# STM32F103RCT6.net
KiCad netlist of a schematic drawn in Altium Designer
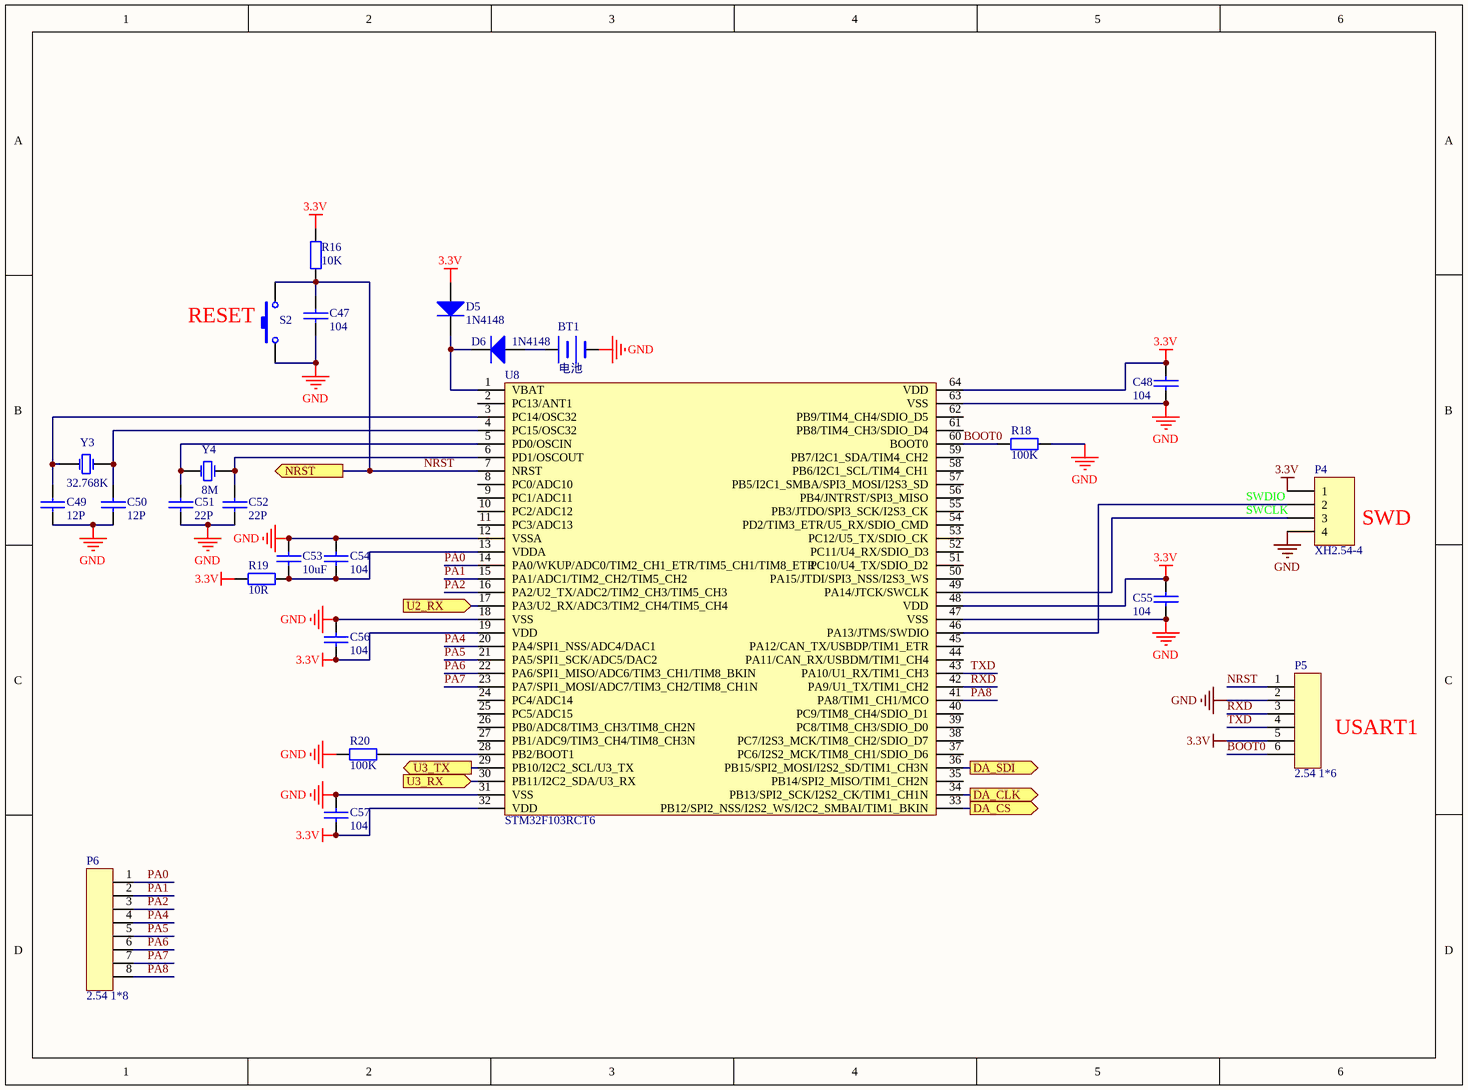
[diagram p0: STM32F103RCT6.SchDoc]

(export (version "E")
  (design (tool "Eeschema 10.0.6"))
  (components
    (comp (ref "BT1") (value "电池") (footprint "BAT-3V") (libsource (lib "Sch_Device_veryaz") (part "电池座 大")))
    (comp (ref "C47")
      (value "104")
      (footprint "0805")
      (libsource (lib "Sch_Device__2010") (part "贴片电容 0805"))
    )
    (comp (ref "C48")
      (value "104")
      (footprint "0805")
      (libsource (lib "Sch_Device__2010") (part "贴片电容 0805"))
    )
    (comp (ref "C49")
      (value "12P")
      (footprint "0805")
      (libsource (lib "Sch_Device__2010") (part "贴片电容 0805"))
    )
    (comp (ref "C50")
      (value "12P")
      (footprint "0805")
      (libsource (lib "Sch_Device__2010") (part "贴片电容 0805"))
    )
    (comp (ref "C51")
      (value "22P")
      (footprint "0805")
      (libsource (lib "Sch_Device__2010") (part "贴片电容 0805"))
    )
    (comp (ref "C52")
      (value "22P")
      (footprint "0805")
      (libsource (lib "Sch_Device__2010") (part "贴片电容 0805"))
    )
    (comp (ref "C53")
      (value "10uF")
      (footprint "1206")
      (libsource (lib "Sch_Device__2010") (part "贴片电容 0805"))
    )
    (comp (ref "C54")
      (value "104")
      (footprint "0805")
      (libsource (lib "Sch_Device__2010") (part "贴片电容 0805"))
    )
    (comp (ref "C55")
      (value "104")
      (footprint "0805")
      (libsource (lib "Sch_Device__2010") (part "贴片电容 0805"))
    )
    (comp (ref "C56")
      (value "104")
      (footprint "0805")
      (libsource (lib "Sch_Device__2010") (part "贴片电容 0805"))
    )
    (comp (ref "C57")
      (value "104")
      (footprint "0805")
      (libsource (lib "Sch_Device__2010") (part "贴片电容 0805"))
    )
    (comp (ref "D5")
      (value "1N4148")
      (footprint "二极管 贴片 IN4148")
      (libsource (lib "") (part "二极管 贴片 1N4148_1"))
    )
    (comp (ref "D6")
      (value "1N4148")
      (footprint "二极管 贴片 IN4148")
      (libsource (lib "Sch_Device_veryaz") (part "二极管 贴片 1N4148"))
    )
    (comp (ref "P4")
      (value "XH2.54-4")
      (footprint "VH2.54_4")
      (libsource (lib "Sch_Device_veryaz") (part "联结件 XH2.54-4"))
    )
    (comp (ref "P5")
      (value "2.54 1*6")
      (footprint "单排插针 2.54 1*6")
      (libsource (lib "Sch_Device_veryaz") (part "联结件 单排插针 2.54 1*6"))
    )
    (comp (ref "P6")
      (value "2.54 1*8")
      (footprint "单排插针 2.54 1*8")
      (libsource (lib "Sch_Device_veryaz") (part "联结件 单排插针 2.54 1*8"))
    )
    (comp (ref "R16") (value "10K") (footprint "0805") (libsource (lib "") (part "贴片电阻 0603_1")))
    (comp (ref "R18")
      (value "100K")
      (footprint "0805")
      (libsource (lib "Sch_Device_Simple") (part "贴片电阻 0805"))
    )
    (comp (ref "R19")
      (value "10R")
      (footprint "0805")
      (libsource (lib "Sch_Device_veryaz") (part "贴片电阻 0603"))
    )
    (comp (ref "R20") (value "100K") (footprint "0805") (libsource (lib "") (part "贴片电阻 0805_1")))
    (comp (ref "S2")
      (value "key")
      (footprint "按键 轻触  6*3")
      (libsource (lib "Sch_Device_veryaz") (part "按键 轻触 3*6"))
    )
    (comp (ref "U8")
      (value "STM32F103RCT6")
      (footprint "Pcb Device_veryaz:LQFP64")
      (libsource (lib "Sch_Device_veryaz") (part "贴片芯片 STM32F103RCT6"))
    )
    (comp (ref "Y3")
      (value "32.768K")
      (footprint "晶振 卧 BCY-W2/D3.1")
      (libsource (lib "Sch_Device_veryaz") (part "晶振 直插矮"))
    )
    (comp (ref "Y4")
      (value "8M")
      (footprint "晶振 BCY-W2/E4.7")
      (libsource (lib "Sch_Device_veryaz") (part "晶振 直插矮"))
    )
  )
  (nets
    (net (code "1") (name "/BOOT0") (class "Default")
      (node (ref "P5") (pin "6") (pinfunction "6_6") (pintype "passive"))
      (node (ref "R18") (pin "2") (pinfunction "2_2") (pintype "passive"))
      (node (ref "U8") (pin "60") (pinfunction "BOOT0_60") (pintype "passive"))
    )
    (net (code "2") (name "/DA_CLK") (class "Default")
      (node (ref "U8") (pin "34") (pinfunction "PB13/SPI2_SCK/I2S2_CK/TIM1_CH1N_34") (pintype "passive"))
    )
    (net (code "3") (name "/DA_CS") (class "Default")
      (node (ref "U8") (pin "33") (pinfunction "PB12/SPI2_NSS/I2S2_WS/I2C2_SMBAI/TIM1_BKIN_33") (pintype "passive"))
    )
    (net (code "4") (name "/DA_SDI") (class "Default")
      (node (ref "U8") (pin "36") (pinfunction "PB15/SPI2_MOSI/I2S2_SD/TIM1_CH3N_36") (pintype "passive"))
    )
    (net (code "5") (name "/NRST") (class "Default")
      (node (ref "C47") (pin "2") (pintype "passive"))
      (node (ref "P5") (pin "1") (pinfunction "1_1") (pintype "passive"))
      (node (ref "R16") (pin "2") (pinfunction "2_2") (pintype "passive"))
      (node (ref "S2") (pin "2") (pinfunction "2_2") (pintype "passive"))
      (node (ref "U8") (pin "7") (pinfunction "NRST_7") (pintype "passive"))
    )
    (net (code "6") (name "/PA0") (class "Default")
      (node (ref "P6") (pin "1") (pinfunction "1_1") (pintype "passive"))
      (node (ref "U8") (pin "14") (pinfunction "PA0/WKUP/ADC0/TIM2_CH1_ETR/TIM5_CH1/TIM8_ETR_14") (pintype "passive"))
    )
    (net (code "7") (name "/PA1") (class "Default")
      (node (ref "P6") (pin "2") (pinfunction "2_2") (pintype "passive"))
      (node (ref "U8") (pin "15") (pinfunction "PA1/ADC1/TIM2_CH2/TIM5_CH2_15") (pintype "passive"))
    )
    (net (code "8") (name "/PA2") (class "Default")
      (node (ref "P6") (pin "3") (pinfunction "3_3") (pintype "passive"))
      (node (ref "U8") (pin "16") (pinfunction "PA2/U2_TX/ADC2/TIM2_CH3/TIM5_CH3_16") (pintype "passive"))
    )
    (net (code "9") (name "/PA4") (class "Default")
      (node (ref "P6") (pin "4") (pinfunction "4_4") (pintype "passive"))
      (node (ref "U8") (pin "20") (pinfunction "PA4/SPI1_NSS/ADC4/DAC1_20") (pintype "passive"))
    )
    (net (code "10") (name "/PA5") (class "Default")
      (node (ref "P6") (pin "5") (pinfunction "5_5") (pintype "passive"))
      (node (ref "U8") (pin "21") (pinfunction "PA5/SPI1_SCK/ADC5/DAC2_21") (pintype "passive"))
    )
    (net (code "11") (name "/PA6") (class "Default")
      (node (ref "P6") (pin "6") (pinfunction "6_6") (pintype "passive"))
      (node (ref "U8") (pin "22") (pinfunction "PA6/SPI1_MISO/ADC6/TIM3_CH1/TIM8_BKIN_22") (pintype "passive"))
    )
    (net (code "12") (name "/PA7") (class "Default")
      (node (ref "P6") (pin "7") (pinfunction "7_7") (pintype "passive"))
      (node (ref "U8") (pin "23") (pinfunction "PA7/SPI1_MOSI/ADC7/TIM3_CH2/TIM8_CH1N_23") (pintype "passive"))
    )
    (net (code "13") (name "/PA8") (class "Default")
      (node (ref "P6") (pin "8") (pinfunction "8_8") (pintype "passive"))
      (node (ref "U8") (pin "41") (pinfunction "PA8/TIM1_CH1/MCO_41") (pintype "passive"))
    )
    (net (code "14") (name "/RXD") (class "Default")
      (node (ref "P5") (pin "3") (pinfunction "3_3") (pintype "passive"))
      (node (ref "U8") (pin "42") (pinfunction "PA9/U1_TX/TIM1_CH2_42") (pintype "passive"))
    )
    (net (code "15") (name "/SWCLK") (class "Default")
      (node (ref "P4") (pin "3") (pinfunction "3_3") (pintype "passive"))
      (node (ref "U8") (pin "49") (pinfunction "PA14/JTCK/SWCLK_49") (pintype "passive"))
    )
    (net (code "16") (name "/SWDIO") (class "Default")
      (node (ref "P4") (pin "2") (pinfunction "2_2") (pintype "passive"))
      (node (ref "U8") (pin "46") (pinfunction "PA13/JTMS/SWDIO_46") (pintype "passive"))
    )
    (net (code "17") (name "/TXD") (class "Default")
      (node (ref "P5") (pin "4") (pinfunction "4_4") (pintype "passive"))
      (node (ref "U8") (pin "43") (pinfunction "PA10/U1_RX/TIM1_CH3_43") (pintype "passive"))
    )
    (net (code "18") (name "/U2_RX") (class "Default")
      (node (ref "U8") (pin "17") (pinfunction "PA3/U2_RX/ADC3/TIM2_CH4/TIM5_CH4_17") (pintype "passive"))
    )
    (net (code "19") (name "/U3_RX") (class "Default")
      (node (ref "U8") (pin "30") (pinfunction "PB11/I2C2_SDA/U3_RX_30") (pintype "passive"))
    )
    (net (code "20") (name "/U3_TX") (class "Default")
      (node (ref "U8") (pin "29") (pinfunction "PB10/I2C2_SCL/U3_TX_29") (pintype "passive"))
    )
    (net (code "21") (name "3.3V") (class "Default")
      (node (ref "C48") (pin "1") (pintype "passive"))
      (node (ref "C55") (pin "1") (pintype "passive"))
      (node (ref "C56") (pin "1") (pintype "passive"))
      (node (ref "C57") (pin "1") (pintype "passive"))
      (node (ref "D5") (pin "1") (pinfunction "A_1") (pintype "passive"))
      (node (ref "P4") (pin "1") (pinfunction "1_1") (pintype "passive"))
      (node (ref "P5") (pin "5") (pinfunction "5_5") (pintype "passive"))
      (node (ref "R16") (pin "1") (pinfunction "1_1") (pintype "passive"))
      (node (ref "R19") (pin "1") (pinfunction "1_1") (pintype "passive"))
      (node (ref "U8") (pin "19") (pinfunction "VDD_19") (pintype "passive"))
      (node (ref "U8") (pin "32") (pinfunction "VDD_32") (pintype "passive"))
      (node (ref "U8") (pin "48") (pinfunction "VDD_48") (pintype "passive"))
      (node (ref "U8") (pin "64") (pinfunction "VDD_64") (pintype "passive"))
    )
    (net (code "22") (name "GND") (class "Default")
      (node (ref "BT1") (pin "2") (pinfunction "-_2") (pintype "passive"))
      (node (ref "C47") (pin "1") (pintype "passive"))
      (node (ref "C48") (pin "2") (pintype "passive"))
      (node (ref "C49") (pin "1") (pintype "passive"))
      (node (ref "C50") (pin "1") (pintype "passive"))
      (node (ref "C51") (pin "1") (pintype "passive"))
      (node (ref "C52") (pin "1") (pintype "passive"))
      (node (ref "C53") (pin "2") (pintype "passive"))
      (node (ref "C54") (pin "2") (pintype "passive"))
      (node (ref "C55") (pin "2") (pintype "passive"))
      (node (ref "C56") (pin "2") (pintype "passive"))
      (node (ref "C57") (pin "2") (pintype "passive"))
      (node (ref "P4") (pin "4") (pinfunction "4_4") (pintype "passive"))
      (node (ref "P5") (pin "2") (pinfunction "2_2") (pintype "passive"))
      (node (ref "R18") (pin "1") (pinfunction "1_1") (pintype "passive"))
      (node (ref "R20") (pin "1") (pinfunction "1_1") (pintype "passive"))
      (node (ref "S2") (pin "1") (pinfunction "1_1") (pintype "passive"))
      (node (ref "U8") (pin "12") (pinfunction "VSSA_12") (pintype "passive"))
      (node (ref "U8") (pin "18") (pinfunction "VSS_18") (pintype "passive"))
      (node (ref "U8") (pin "31") (pinfunction "VSS_31") (pintype "passive"))
      (node (ref "U8") (pin "47") (pinfunction "VSS_47") (pintype "passive"))
      (node (ref "U8") (pin "63") (pinfunction "VSS_63") (pintype "passive"))
    )
    (net (code "23") (name "Net-(BT1-+)") (class "Default")
      (node (ref "BT1") (pin "1") (pinfunction "+_1") (pintype "passive"))
      (node (ref "D6") (pin "1") (pinfunction "A_1") (pintype "passive"))
    )
    (net (code "24") (name "Net-(D5-K)") (class "Default")
      (node (ref "D5") (pin "2") (pinfunction "K_2") (pintype "passive"))
      (node (ref "D6") (pin "2") (pinfunction "K_2") (pintype "passive"))
      (node (ref "U8") (pin "1") (pinfunction "VBAT_1") (pintype "passive"))
    )
    (net (code "25") (name "Net-(U8-PB2{slash}BOOT1)") (class "Default")
      (node (ref "R20") (pin "2") (pinfunction "2_2") (pintype "passive"))
      (node (ref "U8") (pin "28") (pinfunction "PB2/BOOT1_28") (pintype "passive"))
    )
    (net (code "26") (name "Net-(U8-PC14{slash}OSC32)") (class "Default")
      (node (ref "C49") (pin "2") (pintype "passive"))
      (node (ref "U8") (pin "3") (pinfunction "PC14/OSC32_3") (pintype "passive"))
      (node (ref "Y3") (pin "1") (pinfunction "OSC1_1") (pintype "passive"))
    )
    (net (code "27") (name "Net-(U8-PC15{slash}OSC32)") (class "Default")
      (node (ref "C50") (pin "2") (pintype "passive"))
      (node (ref "U8") (pin "4") (pinfunction "PC15/OSC32_4") (pintype "passive"))
      (node (ref "Y3") (pin "2") (pinfunction "OSC2_2") (pintype "passive"))
    )
    (net (code "28") (name "Net-(U8-PD0{slash}OSCIN)") (class "Default")
      (node (ref "C51") (pin "2") (pintype "passive"))
      (node (ref "U8") (pin "5") (pinfunction "PD0/OSCIN_5") (pintype "passive"))
      (node (ref "Y4") (pin "2") (pinfunction "OSC2_2") (pintype "passive"))
    )
    (net (code "29") (name "Net-(U8-PD1{slash}OSCOUT)") (class "Default")
      (node (ref "C52") (pin "2") (pintype "passive"))
      (node (ref "U8") (pin "6") (pinfunction "PD1/OSCOUT_6") (pintype "passive"))
      (node (ref "Y4") (pin "1") (pinfunction "OSC1_1") (pintype "passive"))
    )
    (net (code "30") (name "Net-(U8-VDDA)") (class "Default")
      (node (ref "C53") (pin "1") (pintype "passive"))
      (node (ref "C54") (pin "1") (pintype "passive"))
      (node (ref "R19") (pin "2") (pinfunction "2_2") (pintype "passive"))
      (node (ref "U8") (pin "13") (pinfunction "VDDA_13") (pintype "passive"))
    )
    (net (code "31") (name "unconnected-(U8-PA11{slash}CAN_RX{slash}USBDM{slash}TIM1_CH4-Pad44)") (class "Default")
      (node (ref "U8") (pin "44") (pinfunction "PA11/CAN_RX/USBDM/TIM1_CH4_44") (pintype "passive"))
    )
    (net (code "32") (name "unconnected-(U8-PA12{slash}CAN_TX{slash}USBDP{slash}TIM1_ETR-Pad45)") (class "Default")
      (node (ref "U8") (pin "45") (pinfunction "PA12/CAN_TX/USBDP/TIM1_ETR_45") (pintype "passive"))
    )
    (net (code "33") (name "unconnected-(U8-PA15{slash}JTDI{slash}SPI3_NSS{slash}I2S3_WS-Pad50)") (class "Default")
      (node (ref "U8") (pin "50") (pinfunction "PA15/JTDI/SPI3_NSS/I2S3_WS_50") (pintype "passive"))
    )
    (net (code "34") (name "unconnected-(U8-PB0{slash}ADC8{slash}TIM3_CH3{slash}TIM8_CH2N-Pad26)") (class "Default")
      (node (ref "U8") (pin "26") (pinfunction "PB0/ADC8/TIM3_CH3/TIM8_CH2N_26") (pintype "passive"))
    )
    (net (code "35") (name "unconnected-(U8-PB1{slash}ADC9{slash}TIM3_CH4{slash}TIM8_CH3N-Pad27)") (class "Default")
      (node (ref "U8") (pin "27") (pinfunction "PB1/ADC9/TIM3_CH4/TIM8_CH3N_27") (pintype "passive"))
    )
    (net (code "36") (name "unconnected-(U8-PB3{slash}JTDO{slash}SPI3_SCK{slash}I2S3_CK-Pad55)") (class "Default")
      (node (ref "U8") (pin "55") (pinfunction "PB3/JTDO/SPI3_SCK/I2S3_CK_55") (pintype "passive"))
    )
    (net (code "37") (name "unconnected-(U8-PB4{slash}JNTRST{slash}SPI3_MISO-Pad56)") (class "Default")
      (node (ref "U8") (pin "56") (pinfunction "PB4/JNTRST/SPI3_MISO_56") (pintype "passive"))
    )
    (net (code "38") (name "unconnected-(U8-PB5{slash}I2C1_SMBA{slash}SPI3_MOSI{slash}I2S3_SD-Pad57)") (class "Default")
      (node (ref "U8") (pin "57") (pinfunction "PB5/I2C1_SMBA/SPI3_MOSI/I2S3_SD_57") (pintype "passive"))
    )
    (net (code "39") (name "unconnected-(U8-PB6{slash}I2C1_SCL{slash}TIM4_CH1-Pad58)") (class "Default")
      (node (ref "U8") (pin "58") (pinfunction "PB6/I2C1_SCL/TIM4_CH1_58") (pintype "passive"))
    )
    (net (code "40") (name "unconnected-(U8-PB7{slash}I2C1_SDA{slash}TIM4_CH2-Pad59)") (class "Default")
      (node (ref "U8") (pin "59") (pinfunction "PB7/I2C1_SDA/TIM4_CH2_59") (pintype "passive"))
    )
    (net (code "41") (name "unconnected-(U8-PB8{slash}TIM4_CH3{slash}SDIO_D4-Pad61)") (class "Default")
      (node (ref "U8") (pin "61") (pinfunction "PB8/TIM4_CH3/SDIO_D4_61") (pintype "passive"))
    )
    (net (code "42") (name "unconnected-(U8-PB9{slash}TIM4_CH4{slash}SDIO_D5-Pad62)") (class "Default")
      (node (ref "U8") (pin "62") (pinfunction "PB9/TIM4_CH4/SDIO_D5_62") (pintype "passive"))
    )
    (net (code "43") (name "unconnected-(U8-PB14{slash}SPI2_MISO{slash}TIM1_CH2N-Pad35)") (class "Default")
      (node (ref "U8") (pin "35") (pinfunction "PB14/SPI2_MISO/TIM1_CH2N_35") (pintype "passive"))
    )
    (net (code "44") (name "unconnected-(U8-PC0{slash}ADC10-Pad8)") (class "Default")
      (node (ref "U8") (pin "8") (pinfunction "PC0/ADC10_8") (pintype "passive"))
    )
    (net (code "45") (name "unconnected-(U8-PC1{slash}ADC11-Pad9)") (class "Default")
      (node (ref "U8") (pin "9") (pinfunction "PC1/ADC11_9") (pintype "passive"))
    )
    (net (code "46") (name "unconnected-(U8-PC2{slash}ADC12-Pad10)") (class "Default")
      (node (ref "U8") (pin "10") (pinfunction "PC2/ADC12_10") (pintype "passive"))
    )
    (net (code "47") (name "unconnected-(U8-PC3{slash}ADC13-Pad11)") (class "Default")
      (node (ref "U8") (pin "11") (pinfunction "PC3/ADC13_11") (pintype "passive"))
    )
    (net (code "48") (name "unconnected-(U8-PC4{slash}ADC14-Pad24)") (class "Default")
      (node (ref "U8") (pin "24") (pinfunction "PC4/ADC14_24") (pintype "passive"))
    )
    (net (code "49") (name "unconnected-(U8-PC5{slash}ADC15-Pad25)") (class "Default")
      (node (ref "U8") (pin "25") (pinfunction "PC5/ADC15_25") (pintype "passive"))
    )
    (net (code "50") (name "unconnected-(U8-PC6{slash}I2S2_MCK{slash}TIM8_CH1{slash}SDIO_D6-Pad37)") (class "Default")
      (node (ref "U8") (pin "37") (pinfunction "PC6/I2S2_MCK/TIM8_CH1/SDIO_D6_37") (pintype "passive"))
    )
    (net (code "51") (name "unconnected-(U8-PC7{slash}I2S3_MCK{slash}TIM8_CH2{slash}SDIO_D7-Pad38)") (class "Default")
      (node (ref "U8") (pin "38") (pinfunction "PC7/I2S3_MCK/TIM8_CH2/SDIO_D7_38") (pintype "passive"))
    )
    (net (code "52") (name "unconnected-(U8-PC8{slash}TIM8_CH3{slash}SDIO_D0-Pad39)") (class "Default")
      (node (ref "U8") (pin "39") (pinfunction "PC8/TIM8_CH3/SDIO_D0_39") (pintype "passive"))
    )
    (net (code "53") (name "unconnected-(U8-PC9{slash}TIM8_CH4{slash}SDIO_D1-Pad40)") (class "Default")
      (node (ref "U8") (pin "40") (pinfunction "PC9/TIM8_CH4/SDIO_D1_40") (pintype "passive"))
    )
    (net (code "54") (name "unconnected-(U8-PC10{slash}U4_TX{slash}SDIO_D2-Pad51)") (class "Default")
      (node (ref "U8") (pin "51") (pinfunction "PC10/U4_TX/SDIO_D2_51") (pintype "passive"))
    )
    (net (code "55") (name "unconnected-(U8-PC11{slash}U4_RX{slash}SDIO_D3-Pad52)") (class "Default")
      (node (ref "U8") (pin "52") (pinfunction "PC11/U4_RX/SDIO_D3_52") (pintype "passive"))
    )
    (net (code "56") (name "unconnected-(U8-PC12{slash}U5_TX{slash}SDIO_CK-Pad53)") (class "Default")
      (node (ref "U8") (pin "53") (pinfunction "PC12/U5_TX/SDIO_CK_53") (pintype "passive"))
    )
    (net (code "57") (name "unconnected-(U8-PC13{slash}ANT1-Pad2)") (class "Default")
      (node (ref "U8") (pin "2") (pinfunction "PC13/ANT1_2") (pintype "passive"))
    )
    (net (code "58") (name "unconnected-(U8-PD2{slash}TIM3_ETR{slash}U5_RX{slash}SDIO_CMD-Pad54)") (class "Default")
      (node (ref "U8") (pin "54") (pinfunction "PD2/TIM3_ETR/U5_RX/SDIO_CMD_54") (pintype "passive"))
    )
  )
)
